# TOF_Sensor_Unit_6180.net
KiCad netlist of a schematic drawn in EasyEDA Pro
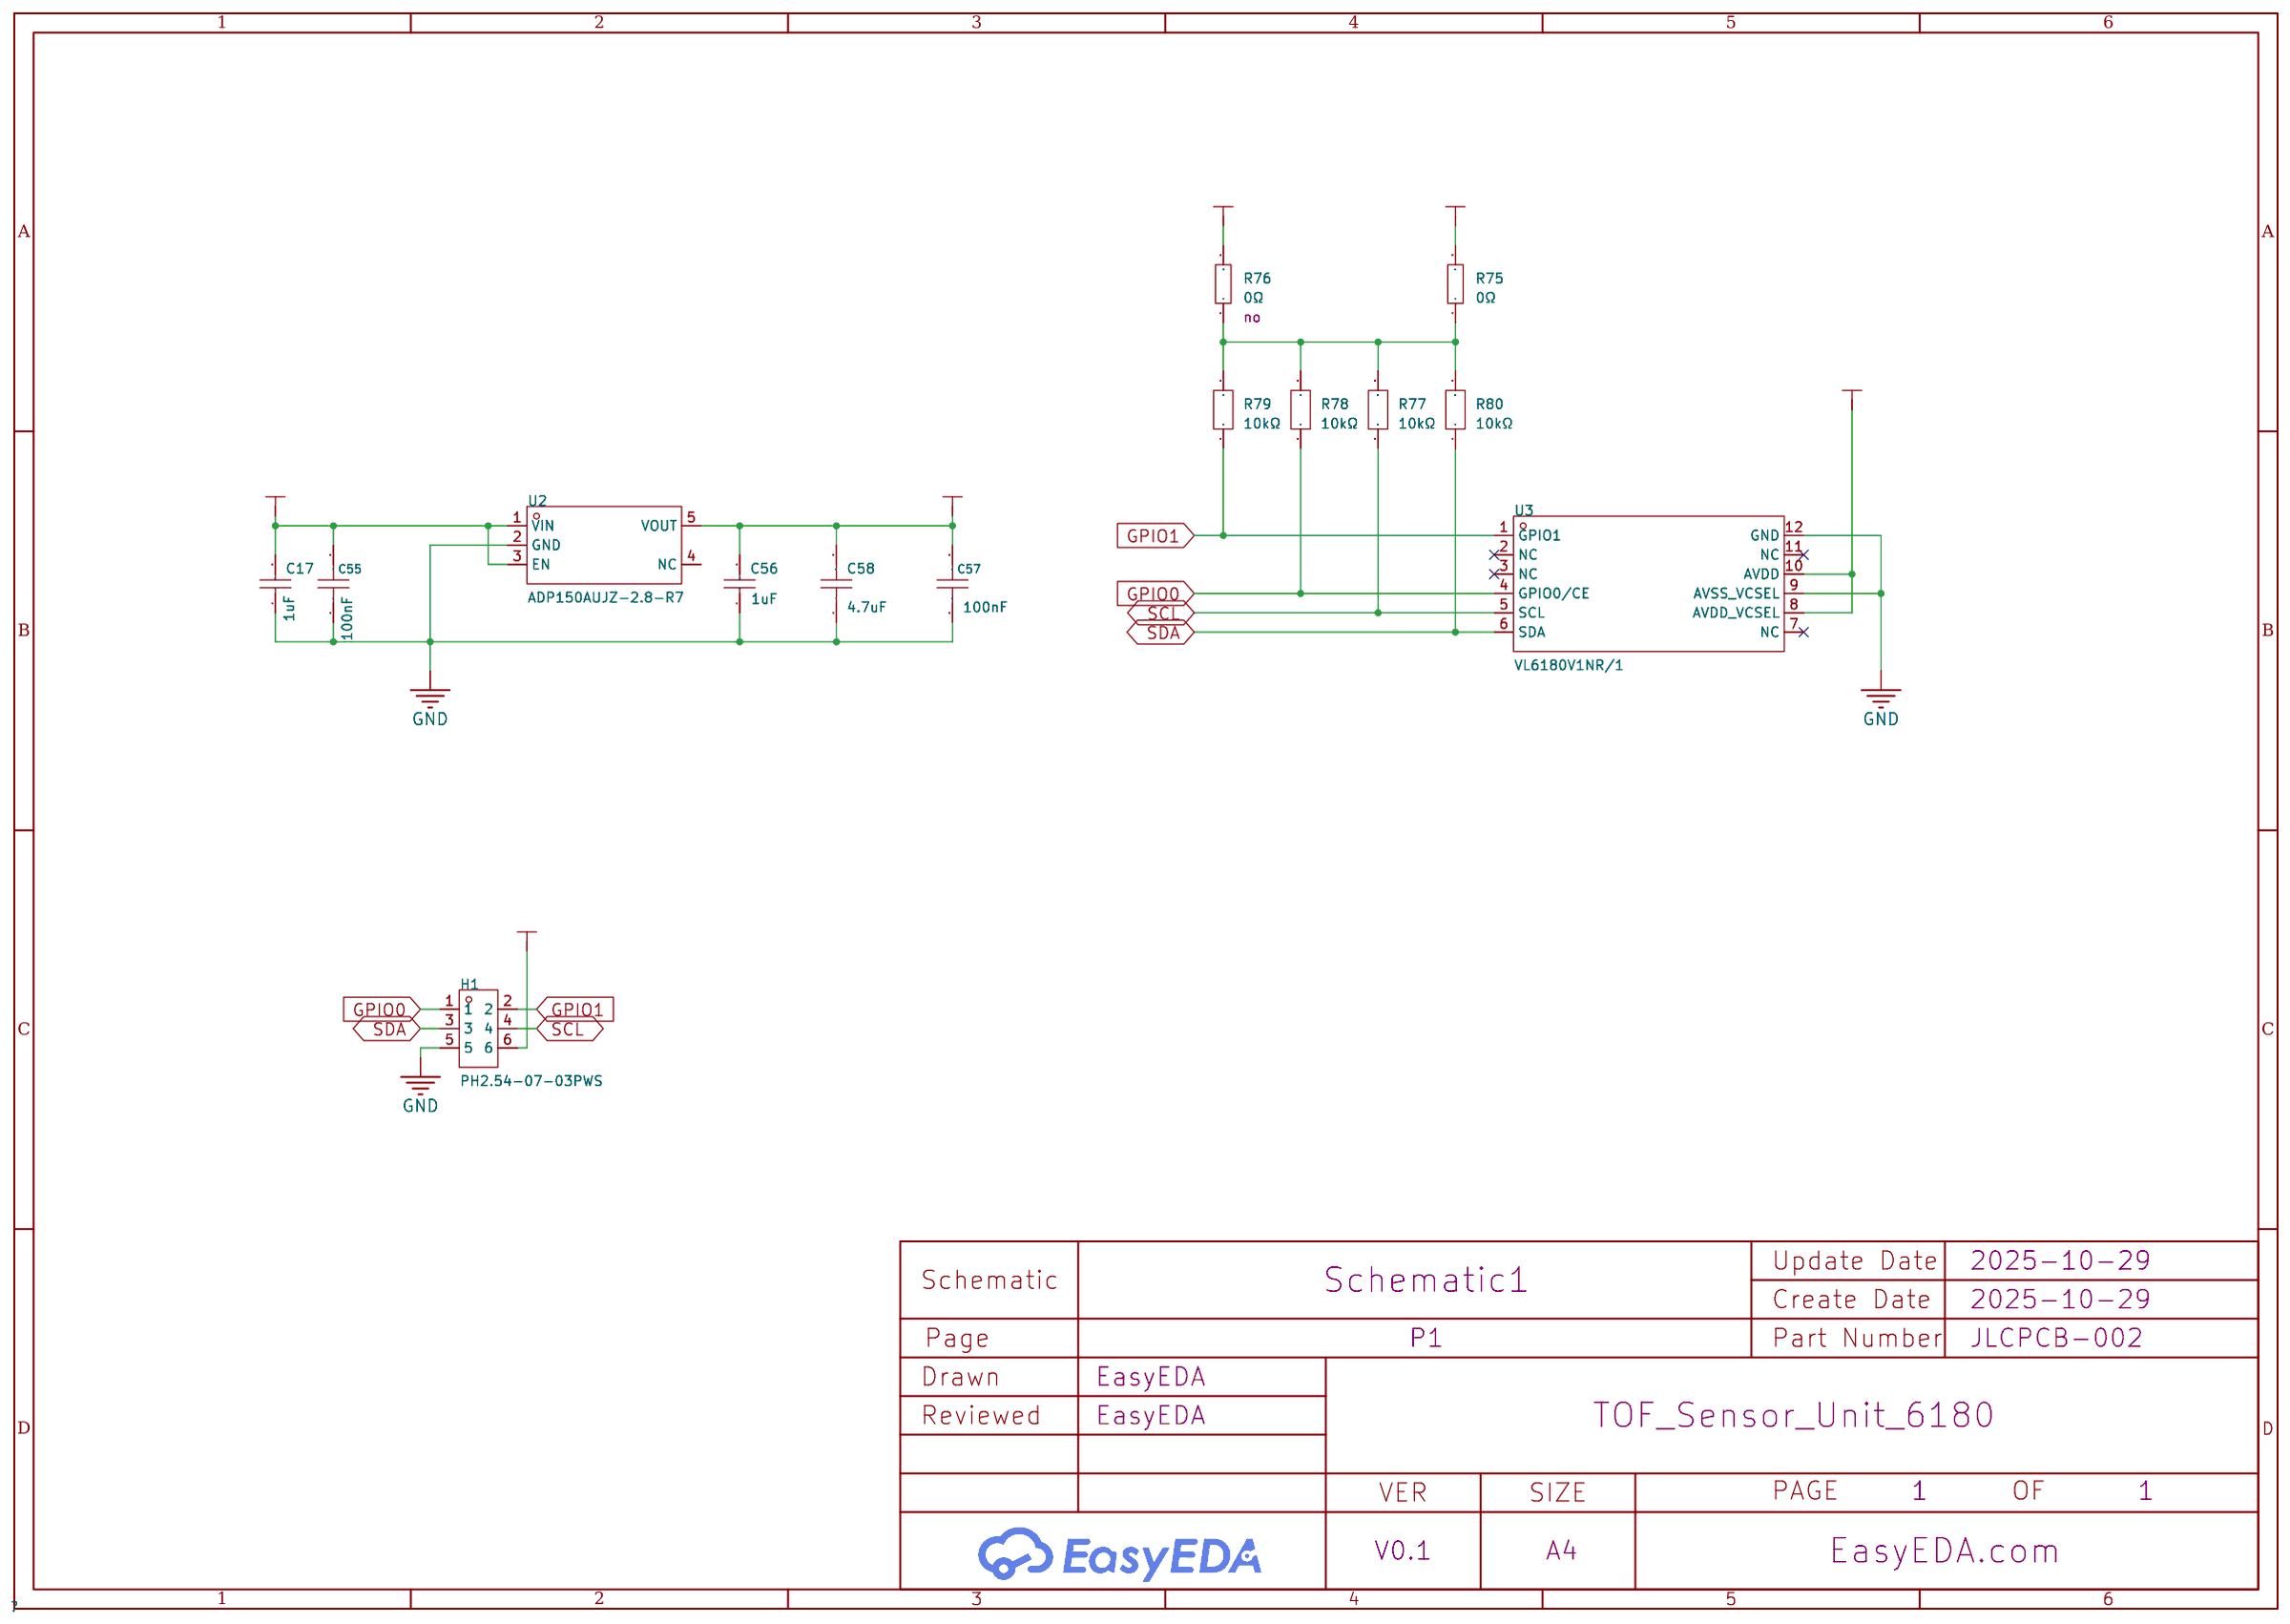
[diagram p0: schematic sheet]

(export (version "E")
  (design (tool "Eeschema 10.0.6"))
  (components
    (comp (ref "C17")
      (value "1uF")
      (footprint "easyedapro:C0603")
      (fields
        (field (name "Manufacturer Part") "CL10A105KO8NNNC")
        (field (name "Manufacturer") "SAMSUNG(三星)")
      )
      (libsource (lib "easyedapro") (part "CL10A105KO8NNNC"))
    )
    (comp (ref "C55")
      (value "100nF")
      (footprint "easyedapro:C0603")
      (fields
        (field (name "Manufacturer Part") "CC0603KRX7R6BB104")
        (field (name "Manufacturer") "YAGEO(国巨)")
      )
      (libsource (lib "easyedapro") (part "CC0603KRX7R6BB104"))
    )
    (comp (ref "C56")
      (value "1uF")
      (footprint "easyedapro:C0603")
      (fields
        (field (name "Manufacturer Part") "CL10A105KO8NNNC")
        (field (name "Manufacturer") "SAMSUNG(三星)")
      )
      (libsource (lib "easyedapro") (part "CL10A105KO8NNNC"))
    )
    (comp (ref "C57")
      (value "100nF")
      (footprint "easyedapro:C0603")
      (fields
        (field (name "Manufacturer Part") "CC0603KRX7R6BB104")
        (field (name "Manufacturer") "YAGEO(国巨)")
      )
      (libsource (lib "easyedapro") (part "CC0603KRX7R6BB104"))
    )
    (comp (ref "C58")
      (value "4.7uF")
      (footprint "easyedapro:C0603")
      (description "Capacitance:4.7uF Tolerance:±10% Tolerance:±10% Voltage Rating:25V Temperature Coefficient:X5R")
      (fields
        (field (name "Manufacturer Part") "CGA0603X5R475K250JT")
        (field (name "Manufacturer") "HRE(芯声)")
      )
      (libsource (lib "easyedapro") (part "CGA0603X5R475K250JT"))
    )
    (comp (ref "H1")
      (value "PH2.54-07-03PWS")
      (footprint "easyedapro:HDR-TH_6P-P2.54-H-M-R2-C3-S2.54-W12.3-N")
      (fields (field (name "Manufacturer") "XUNPU(讯普)"))
      (libsource (lib "easyedapro") (part "PH2.54-07-03PWS"))
    )
    (comp (ref "R75")
      (value "0Ω")
      (footprint "easyedapro:R0603")
      (fields
        (field (name "Manufacturer Part") "0603WAF0000T5E")
        (field (name "Manufacturer") "UNI-ROYAL(厚声)")
      )
      (libsource (lib "easyedapro") (part "0603WAF0000T5E"))
    )
    (comp (ref "R76")
      (value "0Ω")
      (footprint "easyedapro:R0603")
      (fields
        (field (name "Manufacturer Part") "0603WAF0000T5E")
        (field (name "Manufacturer") "UNI-ROYAL(厚声)")
        (field (name "Add into BOM") "no")
      )
      (libsource (lib "easyedapro") (part "0603WAF0000T5E"))
    )
    (comp (ref "R77")
      (value "10kΩ")
      (footprint "easyedapro:R0603")
      (fields (field (name "Manufacturer Part") "FRC0603J103 TS") (field (name "Manufacturer") "FOJAN(富捷)"))
      (libsource (lib "easyedapro") (part "FRC0603J103TS"))
    )
    (comp (ref "R78")
      (value "10kΩ")
      (footprint "easyedapro:R0603")
      (fields (field (name "Manufacturer Part") "FRC0603J103 TS") (field (name "Manufacturer") "FOJAN(富捷)"))
      (libsource (lib "easyedapro") (part "FRC0603J103TS"))
    )
    (comp (ref "R79")
      (value "10kΩ")
      (footprint "easyedapro:R0603")
      (fields (field (name "Manufacturer Part") "FRC0603J103 TS") (field (name "Manufacturer") "FOJAN(富捷)"))
      (libsource (lib "easyedapro") (part "FRC0603J103TS"))
    )
    (comp (ref "R80")
      (value "10kΩ")
      (footprint "easyedapro:R0603")
      (fields (field (name "Manufacturer Part") "FRC0603J103 TS") (field (name "Manufacturer") "FOJAN(富捷)"))
      (libsource (lib "easyedapro") (part "FRC0603J103TS"))
    )
    (comp (ref "U2")
      (value "ADP150AUJZ-2.8-R7")
      (footprint "easyedapro:TSOT-23-5_L2.9-W1.6-P0.95-LS2.8-BL")
      (fields (field (name "Manufacturer") "ADI(亚德诺)"))
      (libsource (lib "easyedapro") (part "ADP150AUJZ-2.8-R7"))
    )
    (comp (ref "U3")
      (value "VL6180V1NR/1")
      (footprint "easyedapro:LGA-12_L4.8-W2.8-P0.75-BL")
      (description "Voltage - Supply:2.6V~3V Voltage - Supply:2.6V~3V Linear Range:0cm~62cm Linear Range:0cm~62cm")
      (fields (field (name "Manufacturer") "ST(意法半导体)"))
      (libsource (lib "easyedapro") (part "VL6180V1NR/1"))
    )
  )
  (nets
    (net (code "1") (name "2V8") (class "Default")
      (node (ref "C56") (pin "2") (pinfunction "2_2") (pintype "input"))
      (node (ref "C57") (pin "2") (pinfunction "2_2") (pintype "input"))
      (node (ref "C58") (pin "2") (pinfunction "2_2") (pintype "unspecified"))
      (node (ref "R75") (pin "2") (pinfunction "2_2") (pintype "input"))
      (node (ref "U2") (pin "5") (pinfunction "VOUT_5") (pintype "unspecified"))
      (node (ref "U3") (pin "10") (pinfunction "AVDD_10") (pintype "unspecified"))
      (node (ref "U3") (pin "8") (pinfunction "AVDD_VCSEL_8") (pintype "unspecified"))
    )
    (net (code "2") (name "3V3") (class "Default")
      (node (ref "C17") (pin "2") (pinfunction "2_2") (pintype "input"))
      (node (ref "C55") (pin "2") (pinfunction "2_2") (pintype "input"))
      (node (ref "H1") (pin "6") (pinfunction "6_6") (pintype "unspecified"))
      (node (ref "R76") (pin "2") (pinfunction "2_2") (pintype "input"))
      (node (ref "U2") (pin "1") (pinfunction "VIN_1") (pintype "unspecified"))
      (node (ref "U2") (pin "3") (pinfunction "EN_3") (pintype "unspecified"))
    )
    (net (code "3") (name "GND") (class "Default")
      (node (ref "C17") (pin "1") (pinfunction "1_1") (pintype "input"))
      (node (ref "C55") (pin "1") (pinfunction "1_1") (pintype "input"))
      (node (ref "C56") (pin "1") (pinfunction "1_1") (pintype "input"))
      (node (ref "C57") (pin "1") (pinfunction "1_1") (pintype "input"))
      (node (ref "C58") (pin "1") (pinfunction "1_1") (pintype "unspecified"))
      (node (ref "H1") (pin "5") (pinfunction "5_5") (pintype "unspecified"))
      (node (ref "U2") (pin "2") (pinfunction "GND_2") (pintype "unspecified"))
      (node (ref "U3") (pin "12") (pinfunction "GND_12") (pintype "unspecified"))
      (node (ref "U3") (pin "9") (pinfunction "AVSS_VCSEL_9") (pintype "unspecified"))
    )
    (net (code "4") (name "GPIO0") (class "Default")
      (node (ref "H1") (pin "1") (pinfunction "1_1") (pintype "unspecified"))
      (node (ref "R78") (pin "1") (pinfunction "1_1") (pintype "unspecified"))
      (node (ref "U3") (pin "4") (pinfunction "GPIO0/CE_4") (pintype "unspecified"))
    )
    (net (code "5") (name "GPIO1") (class "Default")
      (node (ref "H1") (pin "2") (pinfunction "2_2") (pintype "unspecified"))
      (node (ref "R79") (pin "1") (pinfunction "1_1") (pintype "unspecified"))
      (node (ref "U3") (pin "1") (pinfunction "GPIO1_1") (pintype "unspecified"))
    )
    (net (code "6") (name "Net-(R75-Pad1)") (class "Default")
      (node (ref "R75") (pin "1") (pinfunction "1_1") (pintype "input"))
      (node (ref "R76") (pin "1") (pinfunction "1_1") (pintype "input"))
      (node (ref "R77") (pin "2") (pinfunction "2_2") (pintype "unspecified"))
      (node (ref "R78") (pin "2") (pinfunction "2_2") (pintype "unspecified"))
      (node (ref "R79") (pin "2") (pinfunction "2_2") (pintype "unspecified"))
      (node (ref "R80") (pin "2") (pinfunction "2_2") (pintype "unspecified"))
    )
    (net (code "7") (name "SCL") (class "Default")
      (node (ref "H1") (pin "4") (pinfunction "4_4") (pintype "unspecified"))
      (node (ref "R77") (pin "1") (pinfunction "1_1") (pintype "unspecified"))
      (node (ref "U3") (pin "5") (pinfunction "SCL_5") (pintype "unspecified"))
    )
    (net (code "8") (name "SDA") (class "Default")
      (node (ref "H1") (pin "3") (pinfunction "3_3") (pintype "unspecified"))
      (node (ref "R80") (pin "1") (pinfunction "1_1") (pintype "unspecified"))
      (node (ref "U3") (pin "6") (pinfunction "SDA_6") (pintype "unspecified"))
    )
    (net (code "9") (name "unconnected-(U2-NC-Pad4)") (class "Default")
      (node (ref "U2") (pin "4") (pinfunction "NC_4") (pintype "unspecified"))
    )
    (net (code "10") (name "unconnected-(U3-NC-Pad2)") (class "Default")
      (node (ref "U3") (pin "2") (pinfunction "NC_2") (pintype "unspecified+no_connect"))
    )
    (net (code "11") (name "unconnected-(U3-NC-Pad3)") (class "Default")
      (node (ref "U3") (pin "3") (pinfunction "NC_3") (pintype "unspecified+no_connect"))
    )
    (net (code "12") (name "unconnected-(U3-NC-Pad7)") (class "Default")
      (node (ref "U3") (pin "7") (pinfunction "NC_7") (pintype "unspecified+no_connect"))
    )
    (net (code "13") (name "unconnected-(U3-NC-Pad11)") (class "Default")
      (node (ref "U3") (pin "11") (pinfunction "NC_11") (pintype "unspecified+no_connect"))
    )
  )
)
